# trackduino_micro.net
KiCad netlist of a schematic drawn in EAGLE
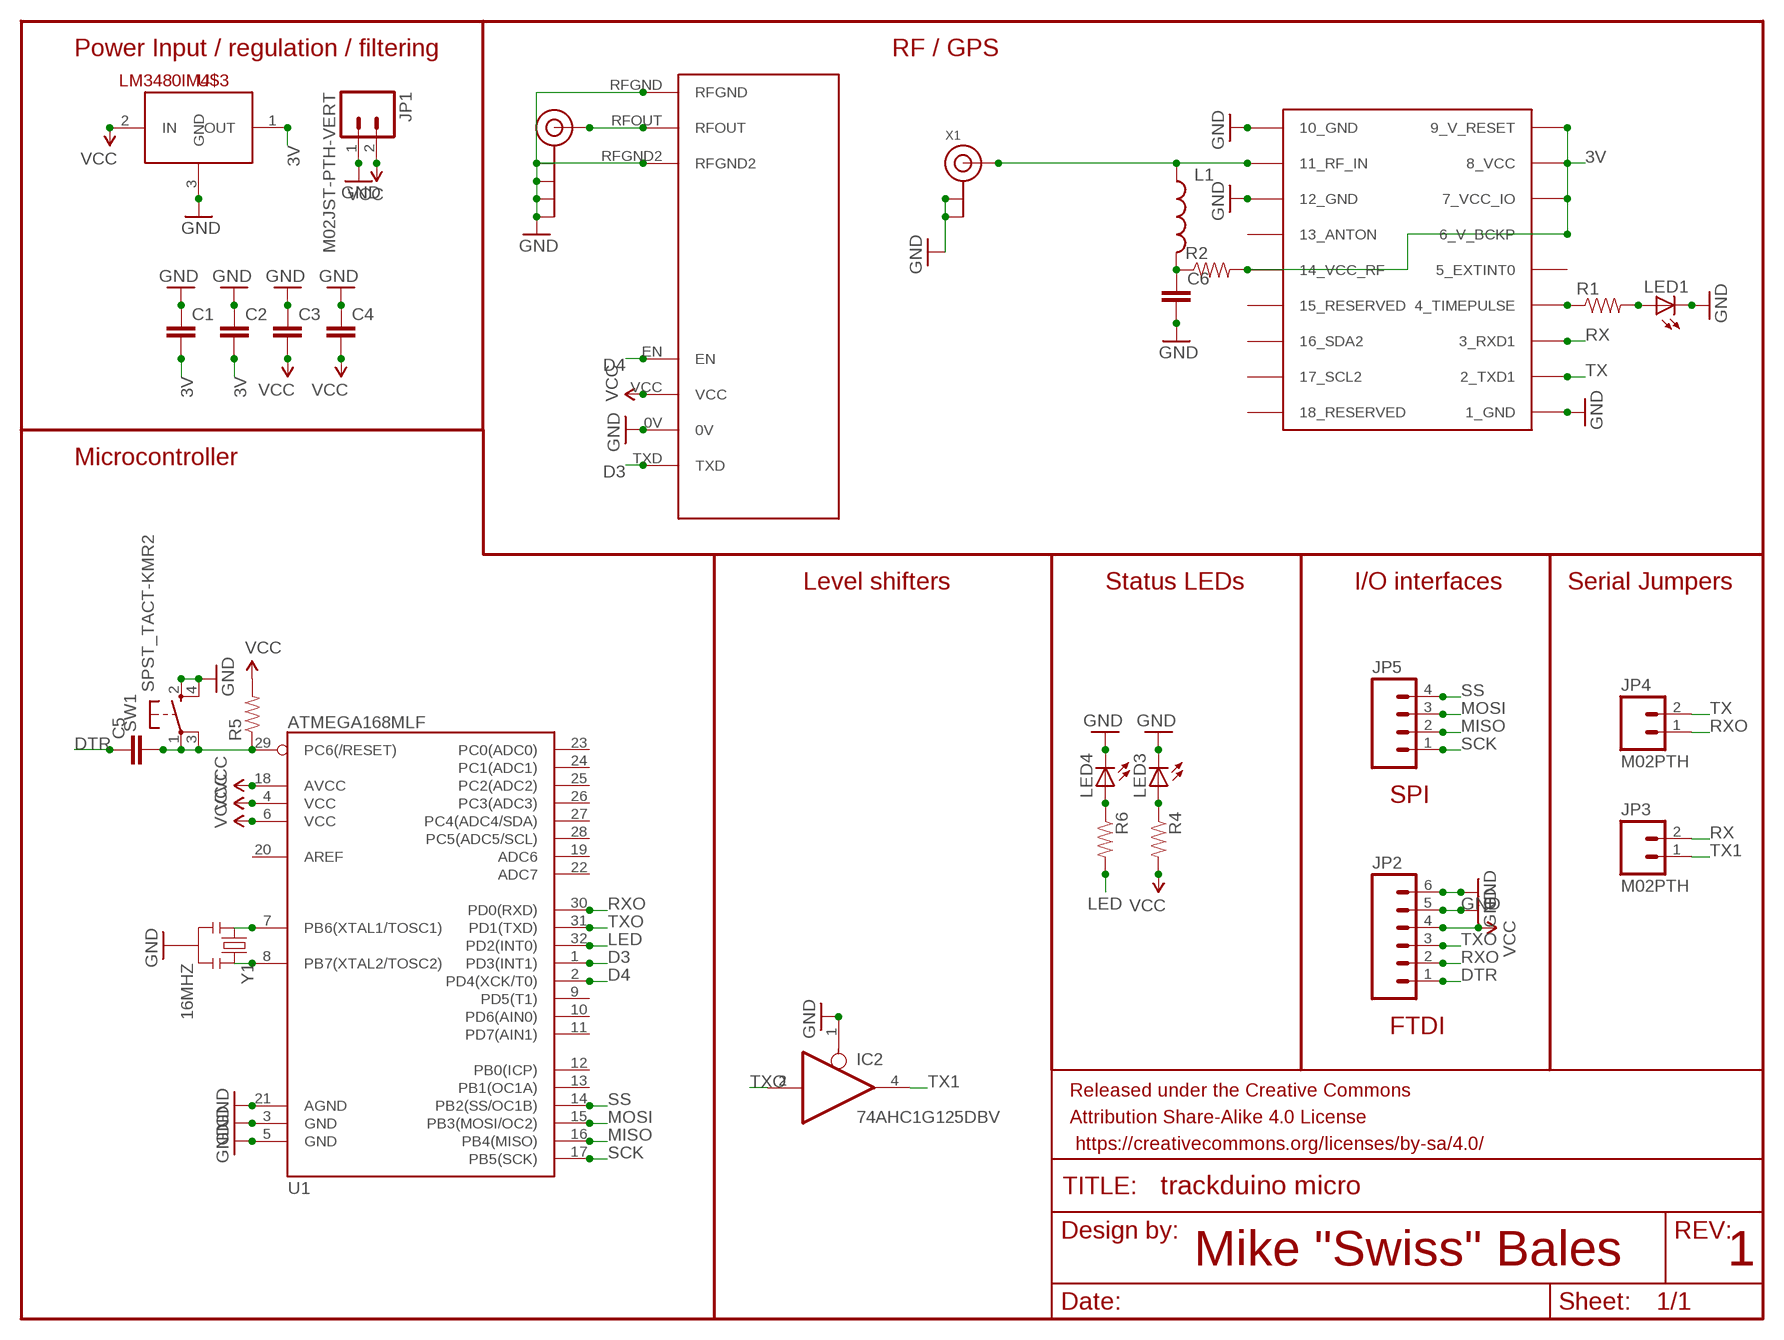
[diagram p0: schematic, sheet 1]

(export (version "E")
  (design (tool "Eeschema 10.0.6"))
  (components
    (comp (ref "C1")
      (value "CAP0805")
      (footprint "eagle-import:0805")
      (libsource (lib "eagle-import") (part "CAP0805"))
    )
    (comp (ref "C2")
      (value "CAP0805")
      (footprint "eagle-import:0805")
      (libsource (lib "eagle-import") (part "CAP0805"))
    )
    (comp (ref "C3")
      (value "CAP0805")
      (footprint "eagle-import:0805")
      (libsource (lib "eagle-import") (part "CAP0805"))
    )
    (comp (ref "C4")
      (value "CAP0805")
      (footprint "eagle-import:0805")
      (libsource (lib "eagle-import") (part "CAP0805"))
    )
    (comp (ref "C5")
      (value "CAP0805")
      (footprint "eagle-import:0805")
      (libsource (lib "eagle-import") (part "CAP0805"))
    )
    (comp (ref "C6")
      (value "CAP0805")
      (footprint "eagle-import:0805")
      (libsource (lib "eagle-import") (part "CAP0805"))
    )
    (comp (ref "FRAME1")
      (value "FRAME-LETTER")
      (footprint "eagle-import:CREATIVE_COMMONS")
      (libsource (lib "eagle-import") (part "FRAME-LETTER"))
    )
    (comp (ref "IC2")
      (value "74AHC1G125DBV")
      (footprint "eagle-import:SOT23-5")
      (libsource (lib "eagle-import") (part "741G125DBVAHC"))
    )
    (comp (ref "J$1")
      (value "SMA_EDGE")
      (footprint "eagle-import:SMA-EDGE")
      (libsource (lib "eagle-import") (part "SMA_EDGE"))
    )
    (comp (ref "JP1")
      (value "M02JST-PTH-VERT")
      (footprint "eagle-import:JST-2-PTH-VERT")
      (libsource (lib "eagle-import") (part "M02JST-PTH-VERT"))
    )
    (comp (ref "JP2")
      (value "M06NO_SILK_FEMALE_PTH")
      (footprint "eagle-import:1X06_NO_SILK")
      (libsource (lib "eagle-import") (part "M06NO_SILK_FEMALE_PTH"))
    )
    (comp (ref "JP3")
      (value "M02PTH")
      (footprint "eagle-import:1X02")
      (libsource (lib "eagle-import") (part "M02PTH"))
    )
    (comp (ref "JP4")
      (value "M02PTH")
      (footprint "eagle-import:1X02")
      (libsource (lib "eagle-import") (part "M02PTH"))
    )
    (comp (ref "JP5")
      (value "M041X04_NO_SILK")
      (footprint "eagle-import:1X04_NO_SILK")
      (libsource (lib "eagle-import") (part "M041X04_NO_SILK"))
    )
    (comp (ref "L1")
      (value "INDUCTOR0805")
      (footprint "eagle-import:0805")
      (libsource (lib "eagle-import") (part "INDUCTOR0805"))
    )
    (comp (ref "LED1")
      (value "LEDCHIP-LED0805")
      (footprint "eagle-import:CHIP-LED0805")
      (libsource (lib "eagle-import") (part "LEDCHIP-LED0805"))
    )
    (comp (ref "LED3")
      (value "LEDCHIP-LED0805")
      (footprint "eagle-import:CHIP-LED0805")
      (libsource (lib "eagle-import") (part "LEDCHIP-LED0805"))
    )
    (comp (ref "LED4")
      (value "LEDCHIP-LED0805")
      (footprint "eagle-import:CHIP-LED0805")
      (libsource (lib "eagle-import") (part "LEDCHIP-LED0805"))
    )
    (comp (ref "R1")
      (value "RESISTOR0805-RES")
      (footprint "eagle-import:0805")
      (libsource (lib "eagle-import") (part "RESISTOR0805-RES"))
    )
    (comp (ref "R2")
      (value "RESISTOR0805-RES")
      (footprint "eagle-import:0805")
      (libsource (lib "eagle-import") (part "RESISTOR0805-RES"))
    )
    (comp (ref "R4")
      (value "RESISTOR0805-RES")
      (footprint "eagle-import:0805")
      (libsource (lib "eagle-import") (part "RESISTOR0805-RES"))
    )
    (comp (ref "R5")
      (value "RESISTOR0805-RES")
      (footprint "eagle-import:0805")
      (libsource (lib "eagle-import") (part "RESISTOR0805-RES"))
    )
    (comp (ref "R6")
      (value "RESISTOR0805-RES")
      (footprint "eagle-import:0805")
      (libsource (lib "eagle-import") (part "RESISTOR0805-RES"))
    )
    (comp (ref "SW1")
      (value "SPST_TACT-KMR2")
      (footprint "eagle-import:KMR2")
      (libsource (lib "eagle-import") (part "SPST_TACT-KMR2"))
    )
    (comp (ref "U$1")
      (value "UBLOX_MAX")
      (footprint "eagle-import:UBLOX_MAX")
      (libsource (lib "eagle-import") (part "UBLOX_MAX"))
    )
    (comp (ref "U$2")
      (value "RADIOMETRIX-HX1")
      (footprint "eagle-import:RADIOMETRIX-HX1")
      (libsource (lib "eagle-import") (part "RADIOMETRIX-HX1"))
    )
    (comp (ref "U$3")
      (value "LM3480IM4")
      (footprint "eagle-import:SOT23-3")
      (libsource (lib "eagle-import") (part "LM3480IM4"))
    )
    (comp (ref "U1")
      (value "ATMEGA168MLF")
      (footprint "eagle-import:MLF32")
      (libsource (lib "eagle-import") (part "ATMEGA168MLF"))
    )
    (comp (ref "X1")
      (value "ANTENNA_U.FL")
      (footprint "eagle-import:U.FL")
      (libsource (lib "eagle-import") (part "ANTENNA_U.FL"))
    )
    (comp (ref "Y1")
      (value "16MHZ")
      (footprint "eagle-import:RESONATOR-SMD")
      (libsource (lib "eagle-import") (part "RESONATOR16MHZ"))
    )
  )
  (nets
    (net (code "1") (name "/3V") (class "Default")
      (node (ref "C1") (pin "2") (pinfunction "2_2") (pintype "passive"))
      (node (ref "C2") (pin "2") (pinfunction "2_2") (pintype "passive"))
      (node (ref "R2") (pin "2") (pinfunction "2_2") (pintype "passive"))
      (node (ref "U$1") (pin "14_VCC_RF") (pinfunction "14_VCC_RF_14_VCC_RF") (pintype "bidirectional"))
      (node (ref "U$1") (pin "6_V_BCKP") (pinfunction "6_V_BCKP_6_V_BCKP") (pintype "bidirectional"))
      (node (ref "U$1") (pin "7_VCC_IO") (pinfunction "7_VCC_IO_7_VCC_IO") (pintype "power_in"))
      (node (ref "U$1") (pin "8_VCC") (pinfunction "8_VCC_8_VCC") (pintype "power_in"))
      (node (ref "U$1") (pin "9_V_RESET") (pinfunction "9_V_RESET_9_V_RESET") (pintype "power_in"))
      (node (ref "U$3") (pin "1") (pinfunction "OUT_1") (pintype "bidirectional"))
    )
    (net (code "2") (name "/D3") (class "Default")
      (node (ref "U$2") (pin "TXD") (pinfunction "TXD_TXD") (pintype "bidirectional"))
      (node (ref "U1") (pin "1") (pinfunction "PD3(INT1)_1") (pintype "bidirectional"))
    )
    (net (code "3") (name "/D4") (class "Default")
      (node (ref "U$2") (pin "EN") (pinfunction "EN_EN") (pintype "bidirectional"))
      (node (ref "U1") (pin "2") (pinfunction "PD4(XCK/T0)_2") (pintype "bidirectional"))
    )
    (net (code "4") (name "/DTR") (class "Default")
      (node (ref "C5") (pin "1") (pinfunction "1_1") (pintype "passive"))
      (node (ref "JP2") (pin "1") (pinfunction "1_1") (pintype "passive"))
    )
    (net (code "5") (name "/LED") (class "Default")
      (node (ref "R6") (pin "2") (pinfunction "2_2") (pintype "passive"))
      (node (ref "U1") (pin "32") (pinfunction "PD2(INT0)_32") (pintype "bidirectional"))
    )
    (net (code "6") (name "/MISO") (class "Default")
      (node (ref "JP5") (pin "2") (pinfunction "2_2") (pintype "passive"))
      (node (ref "U1") (pin "16") (pinfunction "PB4(MISO)_16") (pintype "bidirectional"))
    )
    (net (code "7") (name "/MOSI") (class "Default")
      (node (ref "JP5") (pin "3") (pinfunction "3_3") (pintype "passive"))
      (node (ref "U1") (pin "15") (pinfunction "PB3(MOSI/OC2)_15") (pintype "bidirectional"))
    )
    (net (code "8") (name "/RX") (class "Default")
      (node (ref "JP3") (pin "2") (pinfunction "2_2") (pintype "passive"))
      (node (ref "U$1") (pin "3_RXD1") (pinfunction "3_RXD1_3_RXD1") (pintype "bidirectional"))
    )
    (net (code "9") (name "/RXO") (class "Default")
      (node (ref "JP2") (pin "2") (pinfunction "2_2") (pintype "passive"))
      (node (ref "JP4") (pin "1") (pinfunction "1_1") (pintype "passive"))
      (node (ref "U1") (pin "30") (pinfunction "PD0(RXD)_30") (pintype "bidirectional"))
    )
    (net (code "10") (name "/SCK") (class "Default")
      (node (ref "JP5") (pin "1") (pinfunction "1_1") (pintype "passive"))
      (node (ref "U1") (pin "17") (pinfunction "PB5(SCK)_17") (pintype "bidirectional"))
    )
    (net (code "11") (name "/SS") (class "Default")
      (node (ref "JP5") (pin "4") (pinfunction "4_4") (pintype "passive"))
      (node (ref "U1") (pin "14") (pinfunction "PB2(SS/OC1B)_14") (pintype "bidirectional"))
    )
    (net (code "12") (name "/TX") (class "Default")
      (node (ref "JP4") (pin "2") (pinfunction "2_2") (pintype "passive"))
      (node (ref "U$1") (pin "2_TXD1") (pinfunction "2_TXD1_2_TXD1") (pintype "bidirectional"))
    )
    (net (code "13") (name "/TX1") (class "Default")
      (node (ref "IC2") (pin "4") (pinfunction "O_4") (pintype "tri_state"))
      (node (ref "JP3") (pin "1") (pinfunction "1_1") (pintype "passive"))
    )
    (net (code "14") (name "/TXO") (class "Default")
      (node (ref "IC2") (pin "2") (pinfunction "I_2") (pintype "input"))
      (node (ref "JP2") (pin "3") (pinfunction "3_3") (pintype "passive"))
      (node (ref "U1") (pin "31") (pinfunction "PD1(TXD)_31") (pintype "bidirectional"))
    )
    (net (code "15") (name "GND") (class "Default")
      (node (ref "C1") (pin "1") (pinfunction "1_1") (pintype "passive"))
      (node (ref "C2") (pin "1") (pinfunction "1_1") (pintype "passive"))
      (node (ref "C3") (pin "1") (pinfunction "1_1") (pintype "passive"))
      (node (ref "C4") (pin "1") (pinfunction "1_1") (pintype "passive"))
      (node (ref "C6") (pin "2") (pinfunction "2_2") (pintype "passive"))
      (node (ref "IC2") (pin "1") (pinfunction "OE_1") (pintype "input"))
      (node (ref "J$1") (pin "GND@0") (pinfunction "GND_GND@0") (pintype "bidirectional"))
      (node (ref "J$1") (pin "GND@1") (pinfunction "GND_GND@1") (pintype "bidirectional"))
      (node (ref "J$1") (pin "GND@2") (pinfunction "GND_GND@2") (pintype "bidirectional"))
      (node (ref "J$1") (pin "GND@3") (pinfunction "GND_GND@3") (pintype "bidirectional"))
      (node (ref "JP1") (pin "1") (pinfunction "1_1") (pintype "passive"))
      (node (ref "JP2") (pin "5") (pinfunction "5_5") (pintype "passive"))
      (node (ref "JP2") (pin "6") (pinfunction "6_6") (pintype "passive"))
      (node (ref "LED1") (pin "C") (pinfunction "C_C") (pintype "passive"))
      (node (ref "LED3") (pin "C") (pinfunction "C_C") (pintype "passive"))
      (node (ref "LED4") (pin "C") (pinfunction "C_C") (pintype "passive"))
      (node (ref "SW1") (pin "2") (pinfunction "S_2") (pintype "passive"))
      (node (ref "SW1") (pin "4") (pinfunction "S1_4") (pintype "passive"))
      (node (ref "U$1") (pin "10_GND") (pinfunction "10_GND_10_GND") (pintype "power_in"))
      (node (ref "U$1") (pin "12_GND") (pinfunction "12_GND_12_GND") (pintype "power_in"))
      (node (ref "U$1") (pin "1_GND") (pinfunction "1_GND_1_GND") (pintype "power_in"))
      (node (ref "U$2") (pin "0V") (pinfunction "0V_0V") (pintype "bidirectional"))
      (node (ref "U$2") (pin "RFGND") (pinfunction "RFGND_RFGND") (pintype "bidirectional"))
      (node (ref "U$2") (pin "RFGND2") (pinfunction "RFGND2_RFGND2") (pintype "bidirectional"))
      (node (ref "U$3") (pin "3") (pinfunction "GND_3") (pintype "bidirectional"))
      (node (ref "U1") (pin "21") (pinfunction "AGND_21") (pintype "bidirectional"))
      (node (ref "U1") (pin "3") (pinfunction "GND_3") (pintype "bidirectional"))
      (node (ref "U1") (pin "5") (pinfunction "GND_5") (pintype "bidirectional"))
      (node (ref "X1") (pin "1") (pinfunction "GND_1") (pintype "passive"))
      (node (ref "X1") (pin "2") (pinfunction "GND_2") (pintype "passive"))
      (node (ref "Y1") (pin "2") (pinfunction "2_2") (pintype "passive"))
    )
    (net (code "16") (name "Net-(C6-Pad1)") (class "Default")
      (node (ref "C6") (pin "1") (pinfunction "1_1") (pintype "passive"))
      (node (ref "L1") (pin "2") (pinfunction "2_2") (pintype "passive"))
      (node (ref "R2") (pin "1") (pinfunction "1_1") (pintype "passive"))
    )
    (net (code "17") (name "Net-(J$1-SIGNAL)") (class "Default")
      (node (ref "J$1") (pin "SIG") (pinfunction "SIGNAL_SIG") (pintype "bidirectional"))
      (node (ref "U$2") (pin "RFOUT") (pinfunction "RFOUT_RFOUT") (pintype "bidirectional"))
    )
    (net (code "18") (name "Net-(LED1-PadA)") (class "Default")
      (node (ref "LED1") (pin "A") (pinfunction "A_A") (pintype "passive"))
      (node (ref "R1") (pin "2") (pinfunction "2_2") (pintype "passive"))
    )
    (net (code "19") (name "Net-(LED3-PadA)") (class "Default")
      (node (ref "LED3") (pin "A") (pinfunction "A_A") (pintype "passive"))
      (node (ref "R4") (pin "1") (pinfunction "1_1") (pintype "passive"))
    )
    (net (code "20") (name "Net-(LED4-PadA)") (class "Default")
      (node (ref "LED4") (pin "A") (pinfunction "A_A") (pintype "passive"))
      (node (ref "R6") (pin "1") (pinfunction "1_1") (pintype "passive"))
    )
    (net (code "21") (name "Net-(R1-Pad1)") (class "Default")
      (node (ref "R1") (pin "1") (pinfunction "1_1") (pintype "passive"))
      (node (ref "U$1") (pin "4_TIMEPULSE") (pinfunction "4_TIMEPULSE_4_TIMEPULSE") (pintype "bidirectional"))
    )
    (net (code "22") (name "Net-(SW1-P)") (class "Default")
      (node (ref "C5") (pin "2") (pinfunction "2_2") (pintype "passive"))
      (node (ref "R5") (pin "1") (pinfunction "1_1") (pintype "passive"))
      (node (ref "SW1") (pin "1") (pinfunction "P_1") (pintype "passive"))
      (node (ref "SW1") (pin "3") (pinfunction "P1_3") (pintype "passive"))
      (node (ref "U1") (pin "29") (pinfunction "PC6(/RESET)_29") (pintype "bidirectional"))
    )
    (net (code "23") (name "Net-(U1-PB6(XTAL1{slash}TOSC1))") (class "Default")
      (node (ref "U1") (pin "7") (pinfunction "PB6(XTAL1/TOSC1)_7") (pintype "bidirectional"))
      (node (ref "Y1") (pin "1") (pinfunction "1_1") (pintype "passive"))
    )
    (net (code "24") (name "Net-(U1-PB7(XTAL2{slash}TOSC2))") (class "Default")
      (node (ref "U1") (pin "8") (pinfunction "PB7(XTAL2/TOSC2)_8") (pintype "bidirectional"))
      (node (ref "Y1") (pin "3") (pinfunction "3_3") (pintype "passive"))
    )
    (net (code "25") (name "Net-(X1-SIGNAL)") (class "Default")
      (node (ref "L1") (pin "1") (pinfunction "1_1") (pintype "passive"))
      (node (ref "U$1") (pin "11_RF_IN") (pinfunction "11_RF_IN_11_RF_IN") (pintype "bidirectional"))
      (node (ref "X1") (pin "3") (pinfunction "SIGNAL_3") (pintype "passive"))
    )
    (net (code "26") (name "VCC") (class "Default")
      (node (ref "C3") (pin "2") (pinfunction "2_2") (pintype "passive"))
      (node (ref "C4") (pin "2") (pinfunction "2_2") (pintype "passive"))
      (node (ref "JP1") (pin "2") (pinfunction "2_2") (pintype "passive"))
      (node (ref "JP2") (pin "4") (pinfunction "4_4") (pintype "passive"))
      (node (ref "R4") (pin "2") (pinfunction "2_2") (pintype "passive"))
      (node (ref "R5") (pin "2") (pinfunction "2_2") (pintype "passive"))
      (node (ref "U$2") (pin "VCC") (pinfunction "VCC_VCC") (pintype "bidirectional"))
      (node (ref "U$3") (pin "2") (pinfunction "IN_2") (pintype "bidirectional"))
      (node (ref "U1") (pin "18") (pinfunction "AVCC_18") (pintype "bidirectional"))
      (node (ref "U1") (pin "4") (pinfunction "VCC_4") (pintype "bidirectional"))
      (node (ref "U1") (pin "6") (pinfunction "VCC_6") (pintype "bidirectional"))
    )
    (net (code "27") (name "unconnected-(U$1-Pad5_EXTINT0)") (class "Default")
      (node (ref "U$1") (pin "5_EXTINT0") (pinfunction "5_EXTINT0_5_EXTINT0") (pintype "bidirectional"))
    )
    (net (code "28") (name "unconnected-(U$1-Pad13_ANTON)") (class "Default")
      (node (ref "U$1") (pin "13_ANTON") (pinfunction "13_ANTON_13_ANTON") (pintype "bidirectional"))
    )
    (net (code "29") (name "unconnected-(U$1-Pad15_RESERVED)") (class "Default")
      (node (ref "U$1") (pin "15_RESERVED") (pinfunction "15_RESERVED_15_RESERVED") (pintype "bidirectional"))
    )
    (net (code "30") (name "unconnected-(U$1-Pad16_SDA2)") (class "Default")
      (node (ref "U$1") (pin "16_SDA2") (pinfunction "16_SDA2_16_SDA2") (pintype "bidirectional"))
    )
    (net (code "31") (name "unconnected-(U$1-Pad17_SCL2)") (class "Default")
      (node (ref "U$1") (pin "17_SCL2") (pinfunction "17_SCL2_17_SCL2") (pintype "bidirectional"))
    )
    (net (code "32") (name "unconnected-(U$1-Pad18_RESERVED)") (class "Default")
      (node (ref "U$1") (pin "18_RESERVED") (pinfunction "18_RESERVED_18_RESERVED") (pintype "bidirectional"))
    )
    (net (code "33") (name "unconnected-(U1-ADC6-Pad19)") (class "Default")
      (node (ref "U1") (pin "19") (pinfunction "ADC6_19") (pintype "bidirectional"))
    )
    (net (code "34") (name "unconnected-(U1-ADC7-Pad22)") (class "Default")
      (node (ref "U1") (pin "22") (pinfunction "ADC7_22") (pintype "bidirectional"))
    )
    (net (code "35") (name "unconnected-(U1-AREF-Pad20)") (class "Default")
      (node (ref "U1") (pin "20") (pinfunction "AREF_20") (pintype "bidirectional"))
    )
    (net (code "36") (name "unconnected-(U1-PB0(ICP)-Pad12)") (class "Default")
      (node (ref "U1") (pin "12") (pinfunction "PB0(ICP)_12") (pintype "bidirectional"))
    )
    (net (code "37") (name "unconnected-(U1-PB1(OC1A)-Pad13)") (class "Default")
      (node (ref "U1") (pin "13") (pinfunction "PB1(OC1A)_13") (pintype "bidirectional"))
    )
    (net (code "38") (name "unconnected-(U1-PC0(ADC0)-Pad23)") (class "Default")
      (node (ref "U1") (pin "23") (pinfunction "PC0(ADC0)_23") (pintype "bidirectional"))
    )
    (net (code "39") (name "unconnected-(U1-PC1(ADC1)-Pad24)") (class "Default")
      (node (ref "U1") (pin "24") (pinfunction "PC1(ADC1)_24") (pintype "bidirectional"))
    )
    (net (code "40") (name "unconnected-(U1-PC2(ADC2)-Pad25)") (class "Default")
      (node (ref "U1") (pin "25") (pinfunction "PC2(ADC2)_25") (pintype "bidirectional"))
    )
    (net (code "41") (name "unconnected-(U1-PC3(ADC3)-Pad26)") (class "Default")
      (node (ref "U1") (pin "26") (pinfunction "PC3(ADC3)_26") (pintype "bidirectional"))
    )
    (net (code "42") (name "unconnected-(U1-PC4(ADC4{slash}SDA)-Pad27)") (class "Default")
      (node (ref "U1") (pin "27") (pinfunction "PC4(ADC4/SDA)_27") (pintype "bidirectional"))
    )
    (net (code "43") (name "unconnected-(U1-PC5(ADC5{slash}SCL)-Pad28)") (class "Default")
      (node (ref "U1") (pin "28") (pinfunction "PC5(ADC5/SCL)_28") (pintype "bidirectional"))
    )
    (net (code "44") (name "unconnected-(U1-PD5(T1)-Pad9)") (class "Default")
      (node (ref "U1") (pin "9") (pinfunction "PD5(T1)_9") (pintype "bidirectional"))
    )
    (net (code "45") (name "unconnected-(U1-PD6(AIN0)-Pad10)") (class "Default")
      (node (ref "U1") (pin "10") (pinfunction "PD6(AIN0)_10") (pintype "bidirectional"))
    )
    (net (code "46") (name "unconnected-(U1-PD7(AIN1)-Pad11)") (class "Default")
      (node (ref "U1") (pin "11") (pinfunction "PD7(AIN1)_11") (pintype "bidirectional"))
    )
  )
)
